# scd30_easyeda_pro.net
KiCad netlist of a schematic drawn in EasyEDA Pro
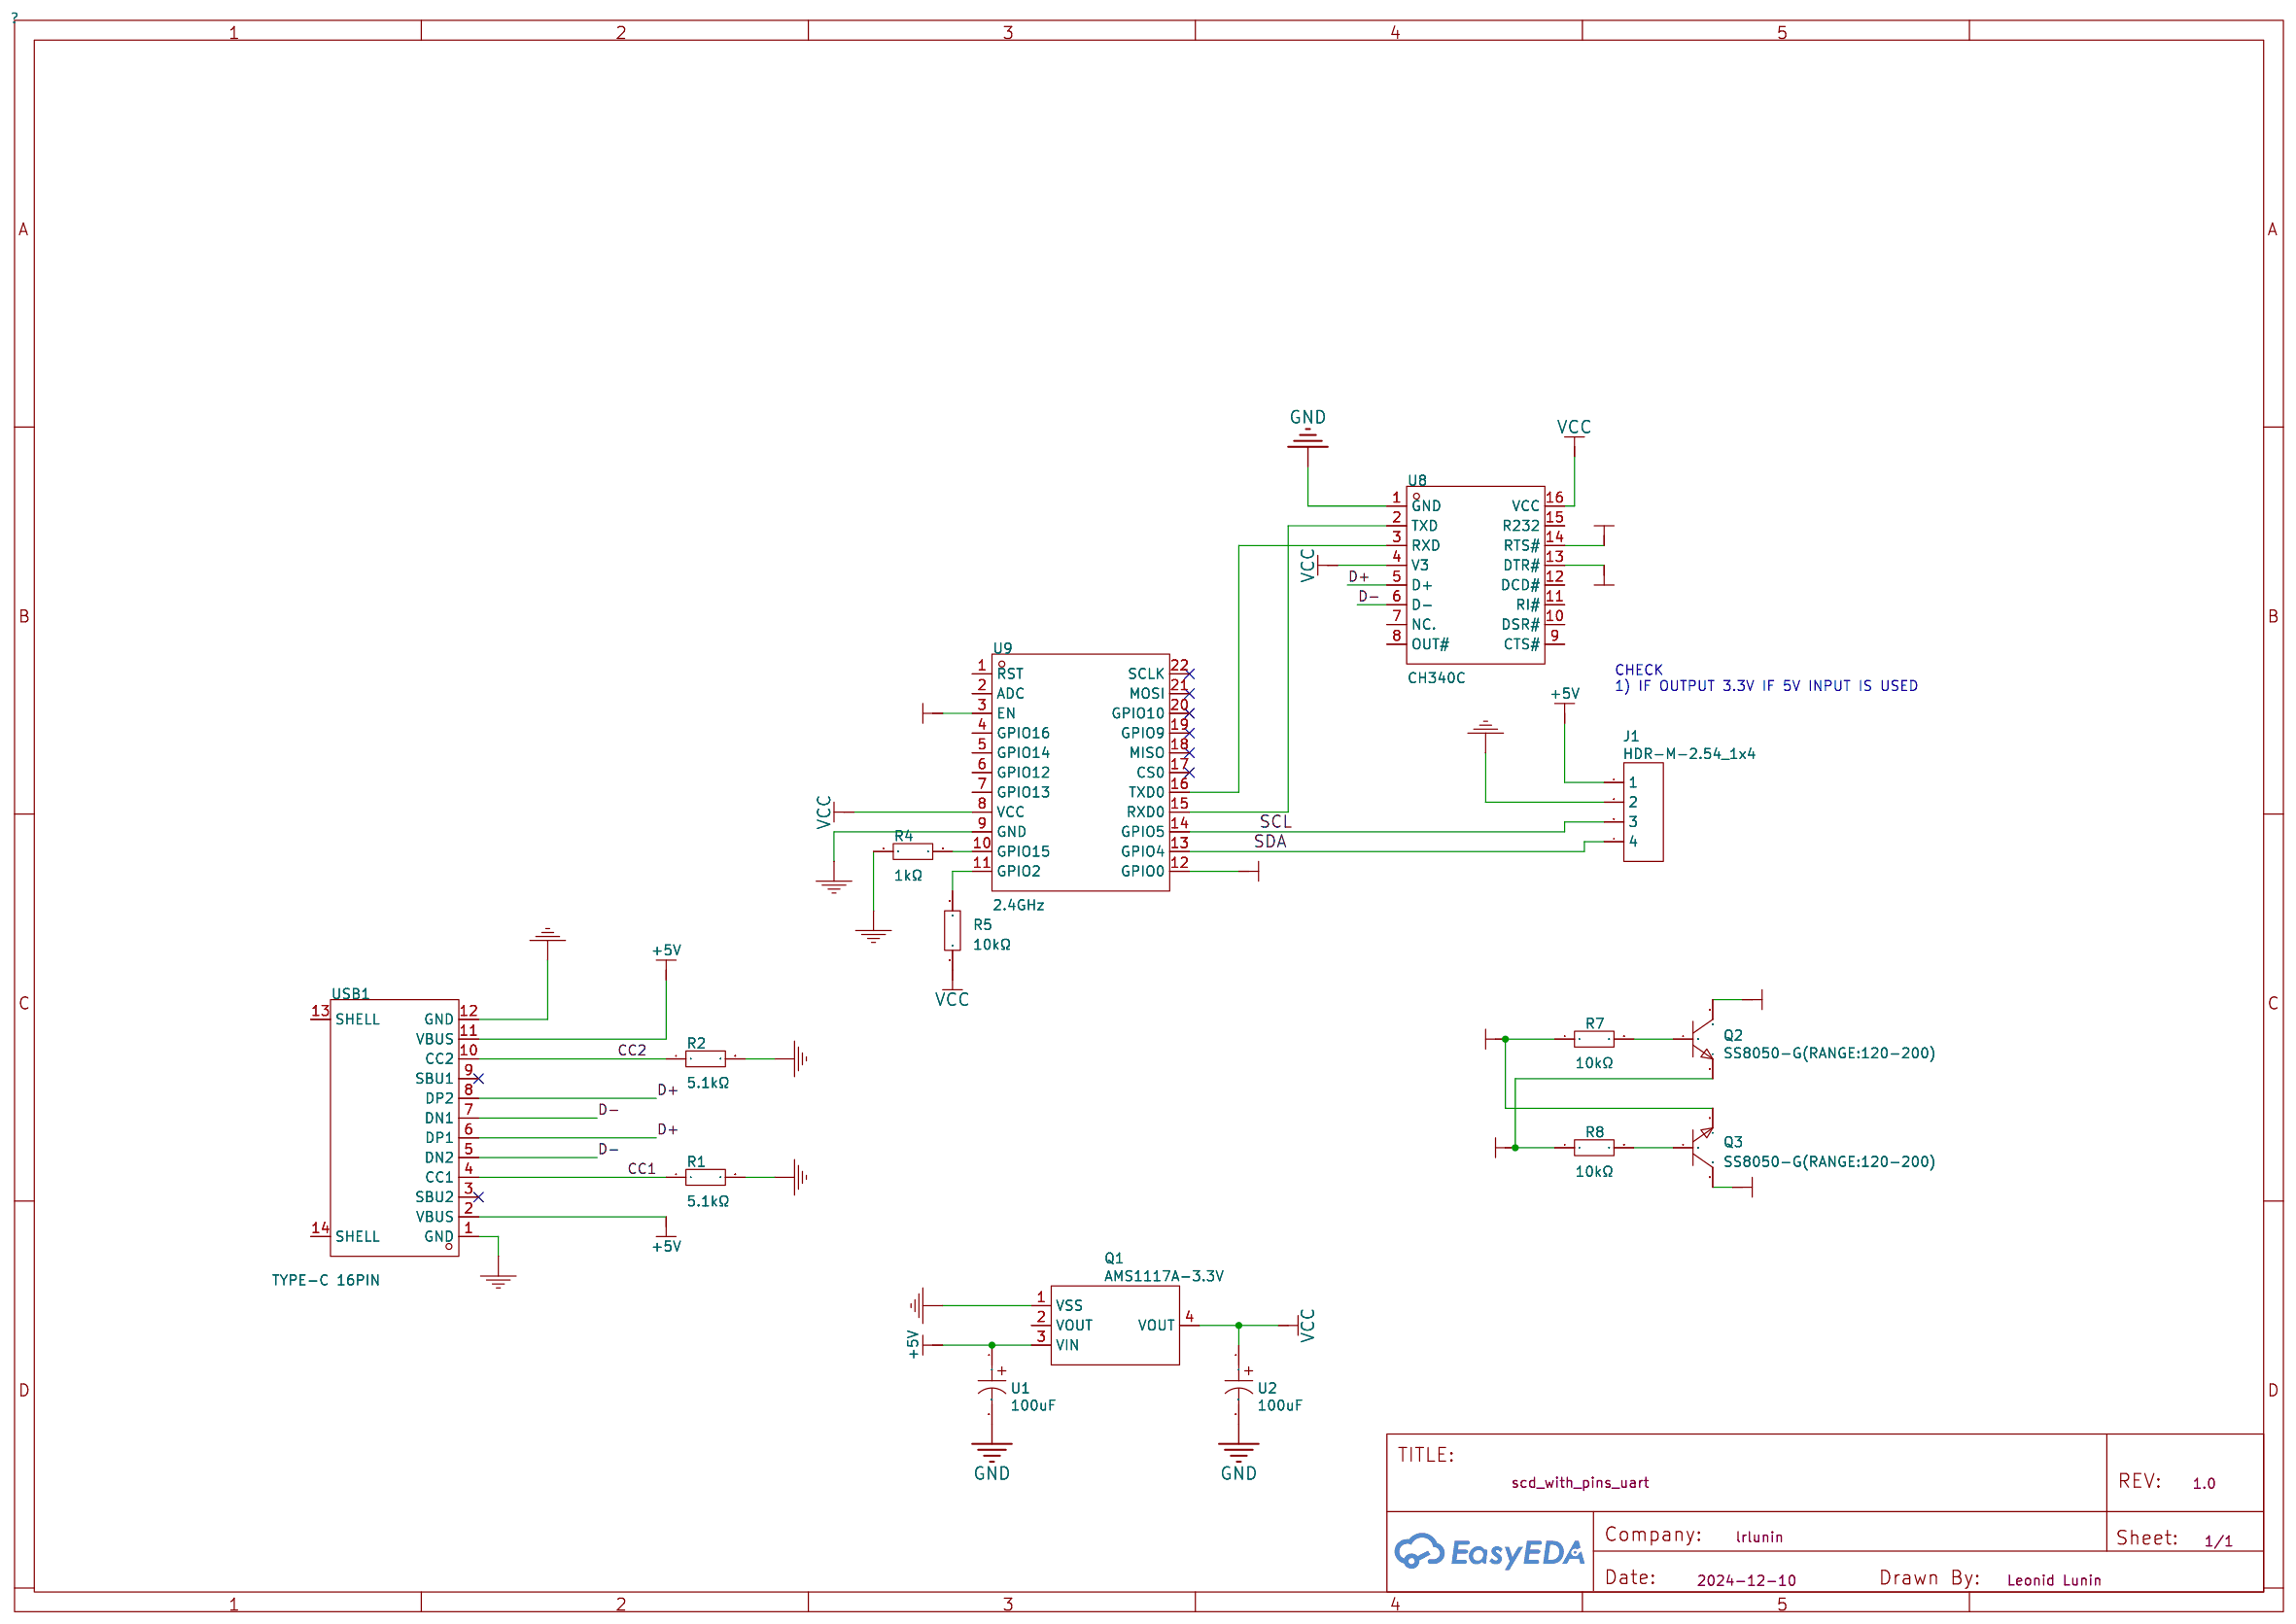
[diagram p0: schematic sheet]

(export (version "E")
  (design (tool "Eeschema 10.0.6"))
  (components
    (comp (ref "J1")
      (value "HDR-M-2.54_1x4")
      (footprint "easyedapro:HDR-M-2.54_1X4")
      (libsource (lib "easyedapro") (part "HDR-M-2.54_1x4"))
    )
    (comp (ref "Q1")
      (value "AMS1117A-3.3V")
      (footprint "easyedapro:SOT-223_L6.3-W3.5-P2.30-LS7.0-BR")
      (fields (field (name "Manufacturer") "HX(恒佳兴)"))
      (libsource (lib "easyedapro") (part "AMS1117A-3.3V"))
    )
    (comp (ref "Q2")
      (value "SS8050-G(RANGE:120-200)")
      (footprint "easyedapro:SOT-23-3_L2.9-W1.3-P1.90-LS2.4-BR")
      (fields (field (name "Manufacturer") "CJ(江苏长电/长晶)"))
      (libsource (lib "easyedapro") (part "SS8050-G"))
    )
    (comp (ref "Q3")
      (value "SS8050-G(RANGE:120-200)")
      (footprint "easyedapro:SOT-23-3_L2.9-W1.3-P1.90-LS2.4-BR")
      (fields (field (name "Manufacturer") "CJ(江苏长电/长晶)"))
      (libsource (lib "easyedapro") (part "SS8050-G"))
    )
    (comp (ref "R1")
      (value "5.1kΩ")
      (footprint "easyedapro:R0402")
      (fields (field (name "Manufacturer Part") "RC0402FR-075K1L") (field (name "Manufacturer") "YAGEO(国巨)"))
      (libsource (lib "easyedapro") (part "RC0402FR-075K1L"))
    )
    (comp (ref "R2")
      (value "5.1kΩ")
      (footprint "easyedapro:R0402")
      (fields (field (name "Manufacturer Part") "RC0402FR-075K1L") (field (name "Manufacturer") "YAGEO(国巨)"))
      (libsource (lib "easyedapro") (part "RC0402FR-075K1L"))
    )
    (comp (ref "R4")
      (value "1kΩ")
      (footprint "easyedapro:R0402")
      (fields (field (name "Manufacturer Part") "RC0402FR-071KL") (field (name "Manufacturer") "YAGEO(国巨)"))
      (libsource (lib "easyedapro") (part "RC0402FR-071KL"))
    )
    (comp (ref "R5")
      (value "10kΩ")
      (footprint "easyedapro:R0402")
      (fields (field (name "Manufacturer Part") "RC0402FR-0710KL") (field (name "Manufacturer") "YAGEO(国巨)"))
      (libsource (lib "easyedapro") (part "RC0402FR-0710KL"))
    )
    (comp (ref "R7")
      (value "10kΩ")
      (footprint "easyedapro:R0402")
      (fields (field (name "Manufacturer Part") "RC0402FR-0710KL") (field (name "Manufacturer") "YAGEO(国巨)"))
      (libsource (lib "easyedapro") (part "RC0402FR-0710KL"))
    )
    (comp (ref "R8")
      (value "10kΩ")
      (footprint "easyedapro:R0402")
      (fields (field (name "Manufacturer Part") "RC0402FR-0710KL") (field (name "Manufacturer") "YAGEO(国巨)"))
      (libsource (lib "easyedapro") (part "RC0402FR-0710KL"))
    )
    (comp (ref "U1")
      (value "100uF")
      (footprint "easyedapro:CAP-SMD_BD6.3-L6.6-W6.6-LS7.2-FD")
      (fields (field (name "Manufacturer") "CapXon(丰宾)"))
      (libsource (lib "easyedapro") (part "100uF"))
    )
    (comp (ref "U2")
      (value "100uF")
      (footprint "easyedapro:CAP-SMD_BD6.3-L6.6-W6.6-LS7.2-FD")
      (fields (field (name "Manufacturer") "CapXon(丰宾)"))
      (libsource (lib "easyedapro") (part "100uF"))
    )
    (comp (ref "U8")
      (value "CH340C")
      (footprint "easyedapro:SOP-16_L10.0-W3.9-P1.27-LS6.0-BL")
      (fields (field (name "Manufacturer") "WCH(南京沁恒)"))
      (libsource (lib "easyedapro") (part "CH340C"))
    )
    (comp (ref "U9")
      (value "2.4GHz")
      (footprint "easyedapro:WIFIM-SMD_ESP-12F-ESP8266MOD")
      (fields
        (field (name "Manufacturer Part") "ESP-12F(ESP8266MOD)")
        (field (name "Manufacturer") "Ai-Thinker(安信可)")
      )
      (libsource (lib "easyedapro") (part "ESP-12F(ESP8266MOD)"))
    )
    (comp (ref "USB1")
      (value "TYPE-C 16PIN")
      (footprint "easyedapro:USB-C-SMD_TYPE-C-6PIN-2MD-073")
      (fields (field (name "Manufacturer") "SHOU HAN(首韩)"))
      (libsource (lib "easyedapro") (part "TYPE-C 16PIN 2MD(073)"))
    )
  )
  (nets
    (net (code "1") (name "+5V") (class "Default")
      (node (ref "J1") (pin "1") (pinfunction "1_1") (pintype "unspecified"))
      (node (ref "Q1") (pin "3") (pinfunction "VIN_3") (pintype "unspecified"))
      (node (ref "U1") (pin "1") (pinfunction "1_1") (pintype "input"))
      (node (ref "USB1") (pin "11") (pinfunction "VBUS_11") (pintype "unspecified"))
      (node (ref "USB1") (pin "2") (pinfunction "VBUS_2") (pintype "unspecified"))
    )
    (net (code "2") (name "/CC1") (class "Default")
      (node (ref "R1") (pin "1") (pinfunction "1_1") (pintype "input"))
      (node (ref "USB1") (pin "4") (pinfunction "CC1_4") (pintype "unspecified"))
    )
    (net (code "3") (name "/CC2") (class "Default")
      (node (ref "R2") (pin "1") (pinfunction "1_1") (pintype "input"))
      (node (ref "USB1") (pin "10") (pinfunction "CC2_10") (pintype "unspecified"))
    )
    (net (code "4") (name "/D+") (class "Default")
      (node (ref "U8") (pin "5") (pinfunction "D+_5") (pintype "unspecified"))
      (node (ref "USB1") (pin "6") (pinfunction "DP1_6") (pintype "unspecified"))
      (node (ref "USB1") (pin "8") (pinfunction "DP2_8") (pintype "unspecified"))
    )
    (net (code "5") (name "/D-") (class "Default")
      (node (ref "U8") (pin "6") (pinfunction "D-_6") (pintype "unspecified"))
      (node (ref "USB1") (pin "5") (pinfunction "DN2_5") (pintype "unspecified"))
      (node (ref "USB1") (pin "7") (pinfunction "DN1_7") (pintype "unspecified"))
    )
    (net (code "6") (name "/SCL") (class "Default")
      (node (ref "J1") (pin "3") (pinfunction "3_3") (pintype "unspecified"))
      (node (ref "U9") (pin "14") (pinfunction "GPIO5_14") (pintype "unspecified"))
    )
    (net (code "7") (name "/SDA") (class "Default")
      (node (ref "J1") (pin "4") (pinfunction "4_4") (pintype "unspecified"))
      (node (ref "U9") (pin "13") (pinfunction "GPIO4_13") (pintype "unspecified"))
    )
    (net (code "8") (name "DTR") (class "Default")
      (node (ref "Q3") (pin "2") (pinfunction "E_2") (pintype "input"))
      (node (ref "R7") (pin "1") (pinfunction "1_1") (pintype "input"))
      (node (ref "U8") (pin "13") (pinfunction "DTR#_13") (pintype "unspecified"))
    )
    (net (code "9") (name "EN") (class "Default")
      (node (ref "Q2") (pin "3") (pinfunction "C_3") (pintype "input"))
      (node (ref "U9") (pin "3") (pinfunction "EN_3") (pintype "unspecified"))
    )
    (net (code "10") (name "GND") (class "Default")
      (node (ref "J1") (pin "2") (pinfunction "2_2") (pintype "unspecified"))
      (node (ref "Q1") (pin "1") (pinfunction "VSS_1") (pintype "unspecified"))
      (node (ref "R1") (pin "2") (pinfunction "2_2") (pintype "input"))
      (node (ref "R2") (pin "2") (pinfunction "2_2") (pintype "input"))
      (node (ref "R4") (pin "1") (pinfunction "1_1") (pintype "input"))
      (node (ref "U1") (pin "2") (pinfunction "2_2") (pintype "input"))
      (node (ref "U2") (pin "2") (pinfunction "2_2") (pintype "input"))
      (node (ref "U8") (pin "1") (pinfunction "GND_1") (pintype "unspecified"))
      (node (ref "U9") (pin "9") (pinfunction "GND_9") (pintype "unspecified"))
      (node (ref "USB1") (pin "1") (pinfunction "GND_1") (pintype "unspecified"))
      (node (ref "USB1") (pin "12") (pinfunction "GND_12") (pintype "unspecified"))
    )
    (net (code "11") (name "IO0") (class "Default")
      (node (ref "Q3") (pin "3") (pinfunction "C_3") (pintype "input"))
      (node (ref "U9") (pin "12") (pinfunction "GPIO0_12") (pintype "unspecified"))
    )
    (net (code "12") (name "Net-(Q2-B)") (class "Default")
      (node (ref "Q2") (pin "1") (pinfunction "B_1") (pintype "input"))
      (node (ref "R7") (pin "2") (pinfunction "2_2") (pintype "input"))
    )
    (net (code "13") (name "Net-(Q3-B)") (class "Default")
      (node (ref "Q3") (pin "1") (pinfunction "B_1") (pintype "input"))
      (node (ref "R8") (pin "2") (pinfunction "2_2") (pintype "input"))
    )
    (net (code "14") (name "Net-(U8-RXD)") (class "Default")
      (node (ref "U8") (pin "3") (pinfunction "RXD_3") (pintype "unspecified"))
      (node (ref "U9") (pin "16") (pinfunction "TXD0_16") (pintype "unspecified"))
    )
    (net (code "15") (name "Net-(U8-TXD)") (class "Default")
      (node (ref "U8") (pin "2") (pinfunction "TXD_2") (pintype "unspecified"))
      (node (ref "U9") (pin "15") (pinfunction "RXD0_15") (pintype "unspecified"))
    )
    (net (code "16") (name "Net-(U9-GPIO2)") (class "Default")
      (node (ref "R5") (pin "2") (pinfunction "2_2") (pintype "input"))
      (node (ref "U9") (pin "11") (pinfunction "GPIO2_11") (pintype "unspecified"))
    )
    (net (code "17") (name "Net-(U9-GPIO15)") (class "Default")
      (node (ref "R4") (pin "2") (pinfunction "2_2") (pintype "input"))
      (node (ref "U9") (pin "10") (pinfunction "GPIO15_10") (pintype "unspecified"))
    )
    (net (code "18") (name "RTS") (class "Default")
      (node (ref "Q2") (pin "2") (pinfunction "E_2") (pintype "input"))
      (node (ref "R8") (pin "1") (pinfunction "1_1") (pintype "input"))
      (node (ref "U8") (pin "14") (pinfunction "RTS#_14") (pintype "unspecified"))
    )
    (net (code "19") (name "VCC") (class "Default")
      (node (ref "Q1") (pin "4") (pinfunction "VOUT_4") (pintype "unspecified"))
      (node (ref "R5") (pin "1") (pinfunction "1_1") (pintype "input"))
      (node (ref "U2") (pin "1") (pinfunction "1_1") (pintype "input"))
      (node (ref "U8") (pin "16") (pinfunction "VCC_16") (pintype "unspecified"))
      (node (ref "U8") (pin "4") (pinfunction "V3_4") (pintype "unspecified"))
      (node (ref "U9") (pin "8") (pinfunction "VCC_8") (pintype "unspecified"))
    )
    (net (code "20") (name "unconnected-(Q1-VOUT-Pad2)") (class "Default")
      (node (ref "Q1") (pin "2") (pinfunction "VOUT_2") (pintype "unspecified"))
    )
    (net (code "21") (name "unconnected-(U8-CTS#-Pad9)") (class "Default")
      (node (ref "U8") (pin "9") (pinfunction "CTS#_9") (pintype "unspecified"))
    )
    (net (code "22") (name "unconnected-(U8-DCD#-Pad12)") (class "Default")
      (node (ref "U8") (pin "12") (pinfunction "DCD#_12") (pintype "unspecified"))
    )
    (net (code "23") (name "unconnected-(U8-DSR#-Pad10)") (class "Default")
      (node (ref "U8") (pin "10") (pinfunction "DSR#_10") (pintype "unspecified"))
    )
    (net (code "24") (name "unconnected-(U8-NC.-Pad7)") (class "Default")
      (node (ref "U8") (pin "7") (pinfunction "NC._7") (pintype "unspecified"))
    )
    (net (code "25") (name "unconnected-(U8-OUT#-Pad8)") (class "Default")
      (node (ref "U8") (pin "8") (pinfunction "OUT#_8") (pintype "unspecified"))
    )
    (net (code "26") (name "unconnected-(U8-R232-Pad15)") (class "Default")
      (node (ref "U8") (pin "15") (pinfunction "R232_15") (pintype "unspecified"))
    )
    (net (code "27") (name "unconnected-(U8-RI#-Pad11)") (class "Default")
      (node (ref "U8") (pin "11") (pinfunction "RI#_11") (pintype "unspecified"))
    )
    (net (code "28") (name "unconnected-(U9-ADC-Pad2)") (class "Default")
      (node (ref "U9") (pin "2") (pinfunction "ADC_2") (pintype "unspecified"))
    )
    (net (code "29") (name "unconnected-(U9-CS0-Pad17)") (class "Default")
      (node (ref "U9") (pin "17") (pinfunction "CS0_17") (pintype "unspecified+no_connect"))
    )
    (net (code "30") (name "unconnected-(U9-GPIO9-Pad19)") (class "Default")
      (node (ref "U9") (pin "19") (pinfunction "GPIO9_19") (pintype "unspecified+no_connect"))
    )
    (net (code "31") (name "unconnected-(U9-GPIO10-Pad20)") (class "Default")
      (node (ref "U9") (pin "20") (pinfunction "GPIO10_20") (pintype "unspecified+no_connect"))
    )
    (net (code "32") (name "unconnected-(U9-GPIO12-Pad6)") (class "Default")
      (node (ref "U9") (pin "6") (pinfunction "GPIO12_6") (pintype "unspecified"))
    )
    (net (code "33") (name "unconnected-(U9-GPIO13-Pad7)") (class "Default")
      (node (ref "U9") (pin "7") (pinfunction "GPIO13_7") (pintype "unspecified"))
    )
    (net (code "34") (name "unconnected-(U9-GPIO14-Pad5)") (class "Default")
      (node (ref "U9") (pin "5") (pinfunction "GPIO14_5") (pintype "unspecified"))
    )
    (net (code "35") (name "unconnected-(U9-GPIO16-Pad4)") (class "Default")
      (node (ref "U9") (pin "4") (pinfunction "GPIO16_4") (pintype "unspecified"))
    )
    (net (code "36") (name "unconnected-(U9-MISO-Pad18)") (class "Default")
      (node (ref "U9") (pin "18") (pinfunction "MISO_18") (pintype "unspecified+no_connect"))
    )
    (net (code "37") (name "unconnected-(U9-MOSI-Pad21)") (class "Default")
      (node (ref "U9") (pin "21") (pinfunction "MOSI_21") (pintype "unspecified+no_connect"))
    )
    (net (code "38") (name "unconnected-(U9-RST-Pad1)") (class "Default")
      (node (ref "U9") (pin "1") (pinfunction "RST_1") (pintype "unspecified"))
    )
    (net (code "39") (name "unconnected-(U9-SCLK-Pad22)") (class "Default")
      (node (ref "U9") (pin "22") (pinfunction "SCLK_22") (pintype "unspecified+no_connect"))
    )
    (net (code "40") (name "unconnected-(USB1-SBU1-Pad9)") (class "Default")
      (node (ref "USB1") (pin "9") (pinfunction "SBU1_9") (pintype "unspecified+no_connect"))
    )
    (net (code "41") (name "unconnected-(USB1-SBU2-Pad3)") (class "Default")
      (node (ref "USB1") (pin "3") (pinfunction "SBU2_3") (pintype "unspecified+no_connect"))
    )
    (net (code "42") (name "unconnected-(USB1-SHELL-Pad13)") (class "Default")
      (node (ref "USB1") (pin "13") (pinfunction "SHELL_13") (pintype "unspecified"))
    )
    (net (code "43") (name "unconnected-(USB1-SHELL-Pad14)") (class "Default")
      (node (ref "USB1") (pin "14") (pinfunction "SHELL_14") (pintype "unspecified"))
    )
  )
)
